# DMX-B.net
KiCad netlist of a schematic drawn in EAGLE
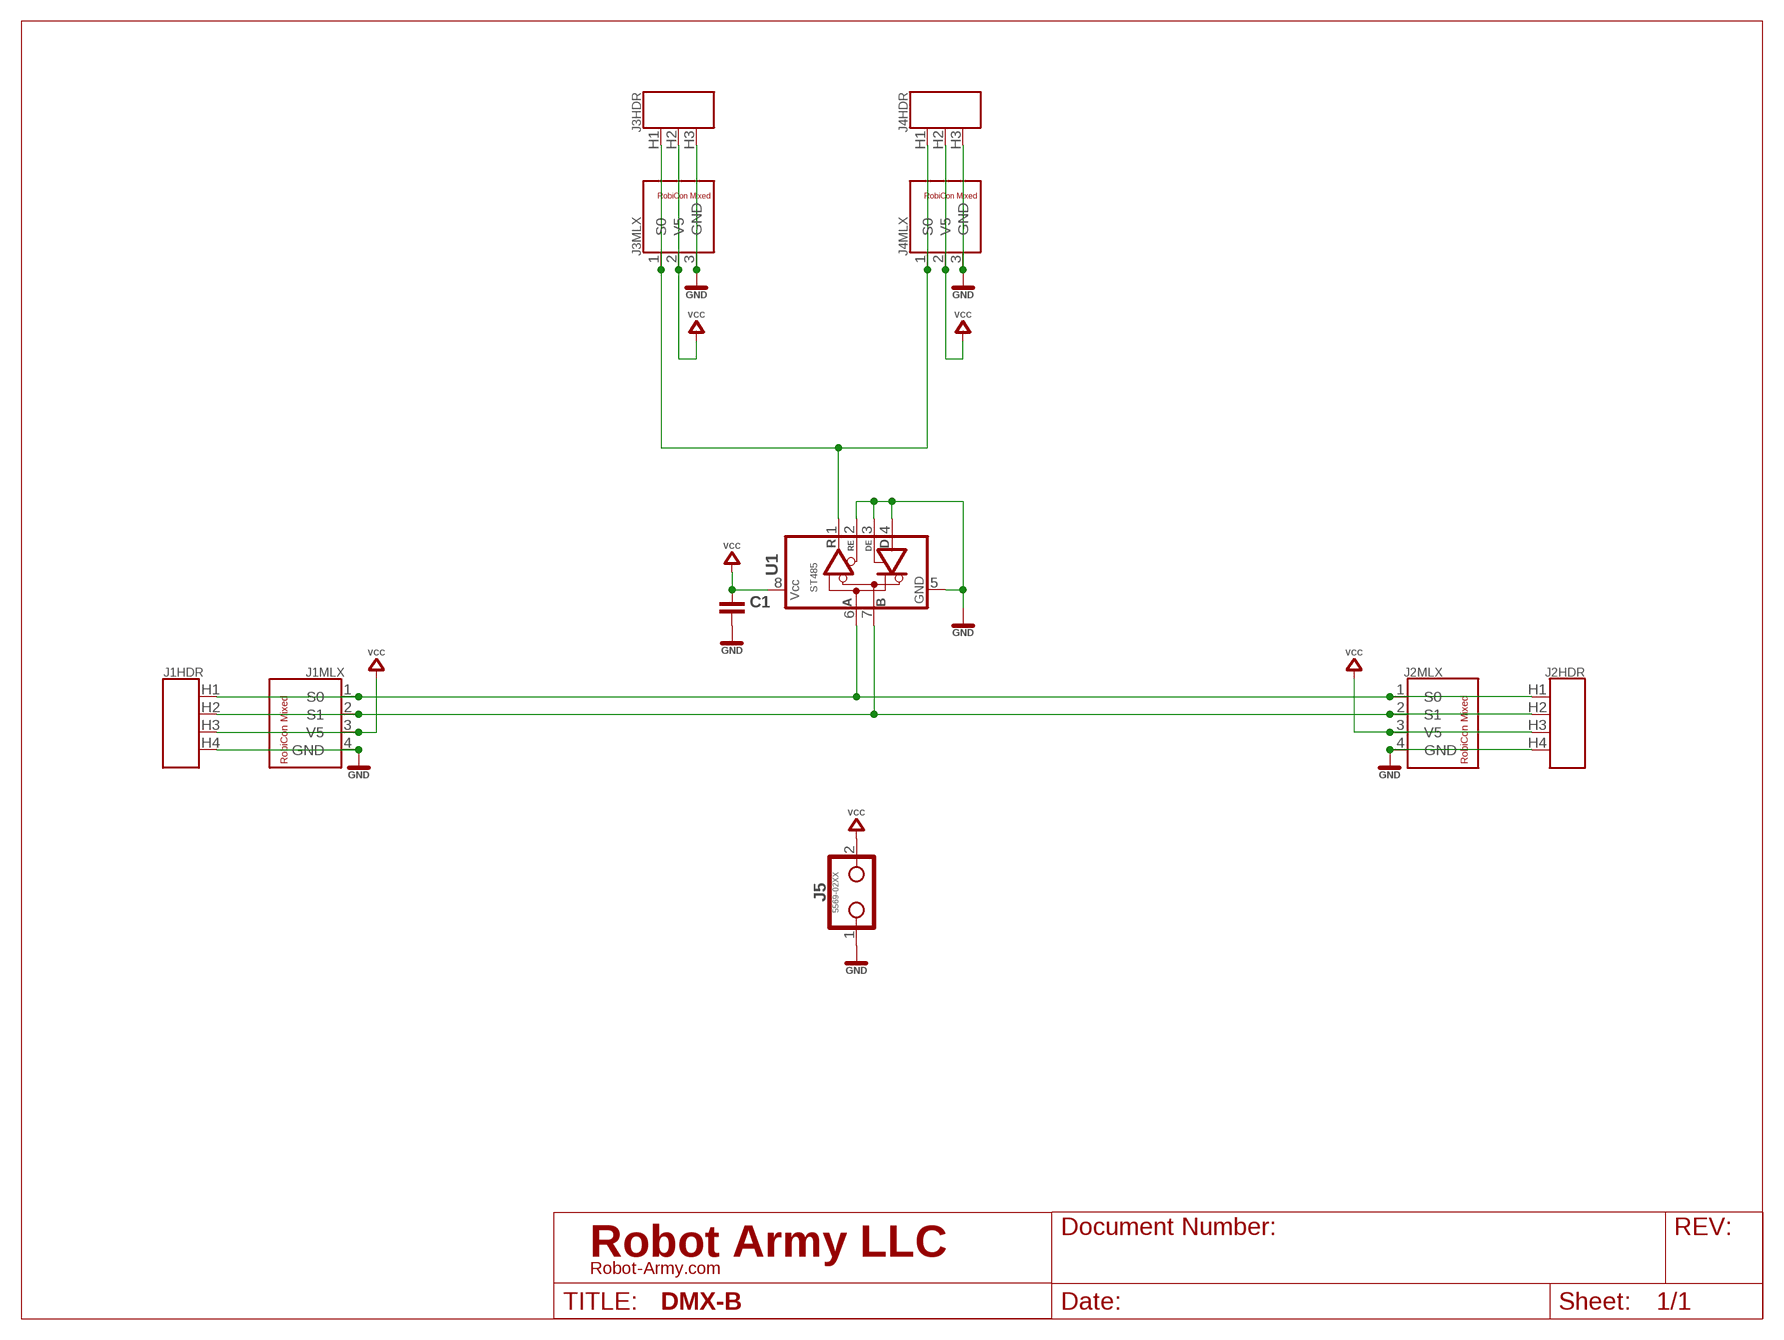
[diagram p0: schematic, sheet 1]

(export (version "E")
  (design (tool "Eeschema 10.0.6"))
  (components
    (comp (ref "C1")
      (value "CAPACITOR0603")
      (footprint "eagle-import:0603")
      (libsource (lib "eagle-import") (part "CAPACITOR0603"))
    )
    (comp (ref "J1")
      (value "ROBICON_M_04P_DUAL")
      (footprint "eagle-import:ROBICON-DUAL-04P")
      (libsource (lib "eagle-import") (part "ROBICON_M_04P_DUAL"))
    )
    (comp (ref "J2")
      (value "ROBICON_M_04P_DUAL")
      (footprint "eagle-import:ROBICON-DUAL-04P")
      (libsource (lib "eagle-import") (part "ROBICON_M_04P_DUAL"))
    )
    (comp (ref "J3")
      (value "ROBICON_M_03P_DUAL")
      (footprint "eagle-import:ROBICON-DUAL-03P")
      (libsource (lib "eagle-import") (part "ROBICON_M_03P_DUAL"))
    )
    (comp (ref "J4")
      (value "ROBICON_M_03P_DUAL")
      (footprint "eagle-import:ROBICON-DUAL-03P")
      (libsource (lib "eagle-import") (part "ROBICON_M_03P_DUAL"))
    )
    (comp (ref "J5")
      (value "5569-02XX")
      (footprint "eagle-import:MOLEX-5569-02XX")
      (libsource (lib "eagle-import") (part "MINIFIT-JR-02P-RA"))
    )
    (comp (ref "U1")
      (value "ST485")
      (footprint "eagle-import:SOP08")
      (libsource (lib "eagle-import") (part "RS485_TRANSCEIVERSO8"))
    )
  )
  (nets
    (net (code "1") (name "GND") (class "Default")
      (node (ref "C1") (pin "2") (pinfunction "2_2") (pintype "passive"))
      (node (ref "J1") (pin "4") (pinfunction "GND_4") (pintype "power_in"))
      (node (ref "J1") (pin "H4") (pinfunction "4_H4") (pintype "bidirectional"))
      (node (ref "J2") (pin "4") (pinfunction "GND_4") (pintype "power_in"))
      (node (ref "J2") (pin "H4") (pinfunction "4_H4") (pintype "bidirectional"))
      (node (ref "J3") (pin "3") (pinfunction "GND_3") (pintype "power_in"))
      (node (ref "J3") (pin "H3") (pinfunction "3_H3") (pintype "bidirectional"))
      (node (ref "J4") (pin "3") (pinfunction "GND_3") (pintype "power_in"))
      (node (ref "J4") (pin "H3") (pinfunction "3_H3") (pintype "bidirectional"))
      (node (ref "J5") (pin "1") (pinfunction "1_1") (pintype "bidirectional"))
      (node (ref "U1") (pin "2") (pinfunction "RE_2") (pintype "input"))
      (node (ref "U1") (pin "3") (pinfunction "DE_3") (pintype "input"))
      (node (ref "U1") (pin "4") (pinfunction "D_4") (pintype "input"))
      (node (ref "U1") (pin "5") (pinfunction "GND_5") (pintype "power_in"))
    )
    (net (code "2") (name "Net-(J1A-1)") (class "Default")
      (node (ref "J1") (pin "1") (pinfunction "S0_1") (pintype "bidirectional"))
      (node (ref "J1") (pin "H1") (pinfunction "1_H1") (pintype "bidirectional"))
      (node (ref "J2") (pin "1") (pinfunction "S0_1") (pintype "bidirectional"))
      (node (ref "J2") (pin "H1") (pinfunction "1_H1") (pintype "bidirectional"))
      (node (ref "U1") (pin "6") (pinfunction "A_6") (pintype "bidirectional"))
    )
    (net (code "3") (name "Net-(J1A-2)") (class "Default")
      (node (ref "J1") (pin "2") (pinfunction "S1_2") (pintype "bidirectional"))
      (node (ref "J1") (pin "H2") (pinfunction "2_H2") (pintype "bidirectional"))
      (node (ref "J2") (pin "2") (pinfunction "S1_2") (pintype "bidirectional"))
      (node (ref "J2") (pin "H2") (pinfunction "2_H2") (pintype "bidirectional"))
      (node (ref "U1") (pin "7") (pinfunction "B_7") (pintype "bidirectional"))
    )
    (net (code "4") (name "Net-(J3A-1)") (class "Default")
      (node (ref "J3") (pin "1") (pinfunction "S0_1") (pintype "bidirectional"))
      (node (ref "J3") (pin "H1") (pinfunction "1_H1") (pintype "bidirectional"))
      (node (ref "J4") (pin "1") (pinfunction "S0_1") (pintype "bidirectional"))
      (node (ref "J4") (pin "H1") (pinfunction "1_H1") (pintype "bidirectional"))
      (node (ref "U1") (pin "1") (pinfunction "R_1") (pintype "output"))
    )
    (net (code "5") (name "VCC") (class "Default")
      (node (ref "C1") (pin "1") (pinfunction "1_1") (pintype "passive"))
      (node (ref "J1") (pin "3") (pinfunction "V5_3") (pintype "power_in"))
      (node (ref "J1") (pin "H3") (pinfunction "3_H3") (pintype "bidirectional"))
      (node (ref "J2") (pin "3") (pinfunction "V5_3") (pintype "power_in"))
      (node (ref "J2") (pin "H3") (pinfunction "3_H3") (pintype "bidirectional"))
      (node (ref "J3") (pin "2") (pinfunction "V5_2") (pintype "power_in"))
      (node (ref "J3") (pin "H2") (pinfunction "2_H2") (pintype "bidirectional"))
      (node (ref "J4") (pin "2") (pinfunction "V5_2") (pintype "power_in"))
      (node (ref "J4") (pin "H2") (pinfunction "2_H2") (pintype "bidirectional"))
      (node (ref "J5") (pin "2") (pinfunction "2_2") (pintype "bidirectional"))
      (node (ref "U1") (pin "8") (pinfunction "VCC_8") (pintype "power_in"))
    )
  )
)
